# PFC_Controller.net
KiCad netlist of a schematic drawn in Altium Designer
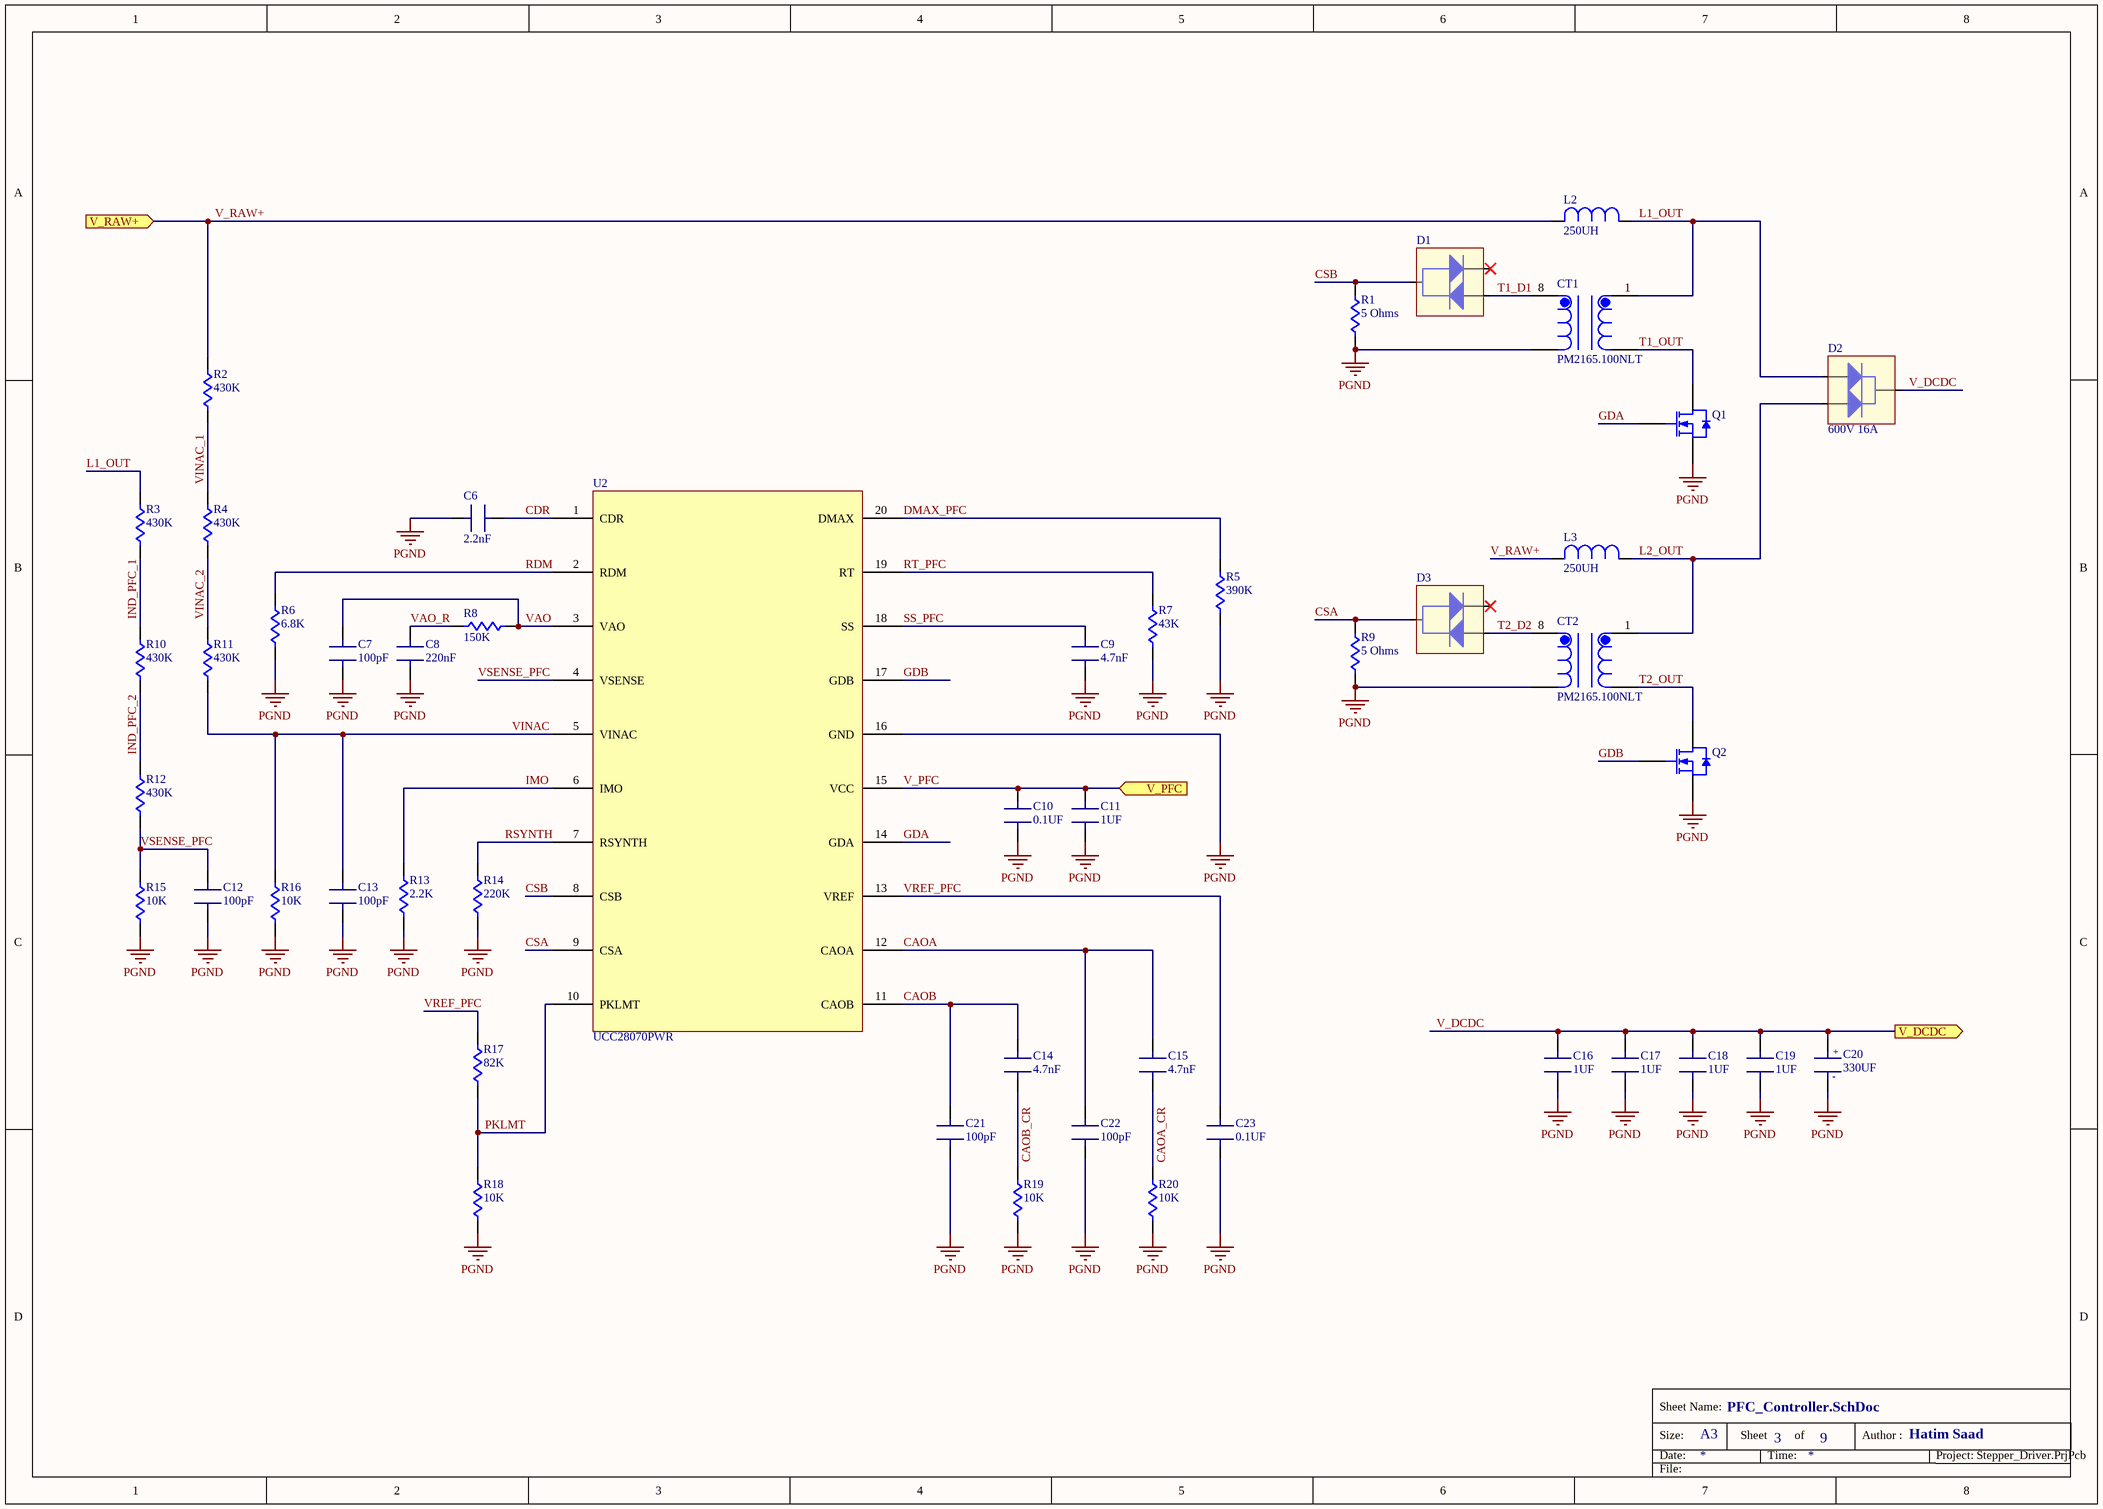
[diagram p0: PFC_Controller.SchDoc]

(export (version "E")
  (design (tool "Eeschema 10.0.6"))
  (components
    (comp (ref "C6")
      (value "2.2nF")
      (footprint "CAP: 0603")
      (description "CAP SMD 0603")
      (libsource (lib "HZSchLib") (part "CAP 0603"))
    )
    (comp (ref "C7")
      (value "100pF")
      (footprint "CAP: 0603")
      (description "CAP SMD 0603")
      (libsource (lib "HZSchLib") (part "CAP 0603"))
    )
    (comp (ref "C8")
      (value "220nF")
      (footprint "CAP: 0603")
      (description "CAP SMD 0603")
      (libsource (lib "HZSchLib") (part "CAP 0603"))
    )
    (comp (ref "C9")
      (value "4.7nF")
      (footprint "CAP: 0603")
      (description "CAP SMD 0603")
      (libsource (lib "HZSchLib") (part "CAP 0603"))
    )
    (comp (ref "C10")
      (value "0.1UF")
      (footprint "CAP: 0603")
      (description "CAP SMD 0603")
      (libsource (lib "HZSchLib") (part "CAP 0603"))
    )
    (comp (ref "C11")
      (value "1UF")
      (footprint "CAP: 0603")
      (description "CAP SMD 0603")
      (libsource (lib "HZSchLib") (part "CAP 0603"))
    )
    (comp (ref "C12")
      (value "100pF")
      (footprint "CAP: 0603")
      (description "CAP SMD 0603")
      (libsource (lib "HZSchLib") (part "CAP 0603"))
    )
    (comp (ref "C13")
      (value "100pF")
      (footprint "CAP: 0603")
      (description "CAP SMD 0603")
      (libsource (lib "HZSchLib") (part "CAP 0603"))
    )
    (comp (ref "C14")
      (value "4.7nF")
      (footprint "CAP: 0603")
      (description "CAP SMD 0603")
      (libsource (lib "HZSchLib") (part "CAP 0603"))
    )
    (comp (ref "C15")
      (value "4.7nF")
      (footprint "CAP: 0603")
      (description "CAP SMD 0603")
      (libsource (lib "HZSchLib") (part "CAP 0603"))
    )
    (comp (ref "C16")
      (value "1UF")
      (footprint "CAP: 2220")
      (description "Multilayer Ceramic Capacitors MLCC - SMD/SMT 1 uF 450 VDC 10% 2220 X7T")
      (libsource (lib "HZSchLib") (part "GR355XD7LP105KW05L"))
    )
    (comp (ref "C17")
      (value "1UF")
      (footprint "CAP: 2220")
      (description "Multilayer Ceramic Capacitors MLCC - SMD/SMT 1 uF 450 VDC 10% 2220 X7T")
      (libsource (lib "HZSchLib") (part "GR355XD7LP105KW05L"))
    )
    (comp (ref "C18")
      (value "1UF")
      (footprint "CAP: 2220")
      (description "Multilayer Ceramic Capacitors MLCC - SMD/SMT 1 uF 450 VDC 10% 2220 X7T")
      (libsource (lib "HZSchLib") (part "GR355XD7LP105KW05L"))
    )
    (comp (ref "C19")
      (value "1UF")
      (footprint "CAP: 2220")
      (description "Multilayer Ceramic Capacitors MLCC - SMD/SMT 1 uF 450 VDC 10% 2220 X7T")
      (libsource (lib "HZSchLib") (part "GR355XD7LP105KW05L"))
    )
    (comp (ref "C20")
      (value "330UF")
      (footprint "CAP: 10MM D: 35MM L: 25MM Snap In")
      (description "Aluminium Electrolytic Capacitors - Snap In 450V 330uF 20% Tol.")
      (libsource (lib "HZSchLib") (part "ESMR451VSN331MA25S"))
    )
    (comp (ref "C21")
      (value "100pF")
      (footprint "CAP: 0603")
      (description "CAP SMD 0603")
      (libsource (lib "HZSchLib") (part "CAP 0603"))
    )
    (comp (ref "C22")
      (value "100pF")
      (footprint "CAP: 0603")
      (description "CAP SMD 0603")
      (libsource (lib "HZSchLib") (part "CAP 0603"))
    )
    (comp (ref "C23")
      (value "0.1UF")
      (footprint "CAP: 0603")
      (description "CAP SMD 0603")
      (libsource (lib "HZSchLib") (part "CAP 0603"))
    )
    (comp (ref "CT1")
      (value "PM2165.100NLT")
      (footprint "CT: PM2165.100NLT")
      (description "Current Transformers 2mH 1000V AEC-Q200 20A DCR=0.75mOhms")
      (libsource (lib "HZSchLib") (part "PM2165.100NLT"))
    )
    (comp (ref "CT2")
      (value "PM2165.100NLT")
      (footprint "CT: PM2165.100NLT")
      (description "Current Transformers 2mH 1000V AEC-Q200 20A DCR=0.75mOhms")
      (libsource (lib "HZSchLib") (part "PM2165.100NLT"))
    )
    (comp (ref "D1")
      (value "BAT54SWT1G")
      (footprint "SOT323")
      (description "Schottky Diodes & Rectifiers 30V 200mW Dual")
      (libsource (lib "HZSchLib") (part "BAT54SWT1G"))
    )
    (comp (ref "D2")
      (value "600V 16A")
      (footprint "D2PAK")
      (description "Schottky Diodes & Rectifiers 600V 16A TO-263 HexFred")
      (libsource (lib "HZSchLib") (part "VS-HFA16TA60CS-M3"))
    )
    (comp (ref "D3")
      (value "BAT54SWT1G")
      (footprint "SOT323")
      (description "Schottky Diodes & Rectifiers 30V 200mW Dual")
      (libsource (lib "HZSchLib") (part "BAT54SWT1G"))
    )
    (comp (ref "L2")
      (value "250UH")
      (footprint "IND: ATCA-08-251M-H")
      (description "FIXED IND 250UH 10A 27 MOHM TH")
      (libsource (lib "HZSchLib") (part "ATCA-08-251M-H"))
    )
    (comp (ref "L3")
      (value "250UH")
      (footprint "IND: ATCA-08-251M-H")
      (description "FIXED IND 250UH 10A 27 MOHM TH")
      (libsource (lib "HZSchLib") (part "ATCA-08-251M-H"))
    )
    (comp (ref "Q1")
      (value "IPT60R099CM8XTMA1")
      (footprint "8-HSOF")
      (description "MOSFETs 600V CoolMOS CM8 Power Transistor")
      (libsource (lib "HZSchLib") (part "IPT60R099CM8XTMA1"))
    )
    (comp (ref "Q2")
      (value "IPT60R099CM8XTMA1")
      (footprint "8-HSOF")
      (description "MOSFETs 600V CoolMOS CM8 Power Transistor")
      (libsource (lib "HZSchLib") (part "IPT60R099CM8XTMA1"))
    )
    (comp (ref "R1")
      (value "5 Ohms")
      (footprint "RES: 1206")
      (description "Current Sense Resistors - SMD 5Ohms 1206 1W 1% Thin Curr Sens AEC-Q200")
      (libsource (lib "HZSchLib") (part "CSRT1206FT5R00"))
    )
    (comp (ref "R2")
      (value "430K")
      (footprint "RES: 2512")
      (description "RES SMD 2512")
      (libsource (lib "HZSchLib") (part "RES 2512"))
    )
    (comp (ref "R3")
      (value "430K")
      (footprint "RES: 2512")
      (description "RES SMD 2512")
      (libsource (lib "HZSchLib") (part "RES 2512"))
    )
    (comp (ref "R4")
      (value "430K")
      (footprint "RES: 2512")
      (description "RES SMD 2512")
      (libsource (lib "HZSchLib") (part "RES 2512"))
    )
    (comp (ref "R5")
      (value "390K")
      (footprint "RES: 0603")
      (description "RES SMD 0603")
      (libsource (lib "HZSchLib") (part "RES 0603"))
    )
    (comp (ref "R6")
      (value "6.8K")
      (footprint "RES: 0603")
      (description "RES SMD 0603")
      (libsource (lib "HZSchLib") (part "RES 0603"))
    )
    (comp (ref "R7")
      (value "43K")
      (footprint "RES: 0603")
      (description "RES SMD 0603")
      (libsource (lib "HZSchLib") (part "RES 0603"))
    )
    (comp (ref "R8")
      (value "150K")
      (footprint "RES: 0603")
      (description "RES SMD 0603")
      (libsource (lib "HZSchLib") (part "RES 0603"))
    )
    (comp (ref "R9")
      (value "5 Ohms")
      (footprint "RES: 1206")
      (description "Current Sense Resistors - SMD 5Ohms 1206 1W 1% Thin Curr Sens AEC-Q200")
      (libsource (lib "HZSchLib") (part "CSRT1206FT5R00"))
    )
    (comp (ref "R10")
      (value "430K")
      (footprint "RES: 2512")
      (description "RES SMD 2512")
      (libsource (lib "HZSchLib") (part "RES 2512"))
    )
    (comp (ref "R11")
      (value "430K")
      (footprint "RES: 2512")
      (description "RES SMD 2512")
      (libsource (lib "HZSchLib") (part "RES 2512"))
    )
    (comp (ref "R12")
      (value "430K")
      (footprint "RES: 2512")
      (description "RES SMD 2512")
      (libsource (lib "HZSchLib") (part "RES 2512"))
    )
    (comp (ref "R13")
      (value "2.2K")
      (footprint "RES: 0603")
      (description "RES SMD 0603")
      (libsource (lib "HZSchLib") (part "RES 0603"))
    )
    (comp (ref "R14")
      (value "220K")
      (footprint "RES: 0603")
      (description "RES SMD 0603")
      (libsource (lib "HZSchLib") (part "RES 0603"))
    )
    (comp (ref "R15")
      (value "10K")
      (footprint "RES: 0603")
      (description "RES SMD 0603")
      (libsource (lib "HZSchLib") (part "RES 0603"))
    )
    (comp (ref "R16")
      (value "10K")
      (footprint "RES: 0603")
      (description "RES SMD 0603")
      (libsource (lib "HZSchLib") (part "RES 0603"))
    )
    (comp (ref "R17")
      (value "82K")
      (footprint "RES: 0603")
      (description "RES SMD 0603")
      (libsource (lib "HZSchLib") (part "RES 0603"))
    )
    (comp (ref "R18")
      (value "10K")
      (footprint "RES: 0603")
      (description "RES SMD 0603")
      (libsource (lib "HZSchLib") (part "RES 0603"))
    )
    (comp (ref "R19")
      (value "10K")
      (footprint "RES: 0603")
      (description "RES SMD 0603")
      (libsource (lib "HZSchLib") (part "RES 0603"))
    )
    (comp (ref "R20")
      (value "10K")
      (footprint "RES: 0603")
      (description "RES SMD 0603")
      (libsource (lib "HZSchLib") (part "RES 0603"))
    )
    (comp (ref "U2")
      (value "UCC28070PWR")
      (footprint "20-TSSOP")
      (description "Power Factor Correction - PFC 2Phase Interleaved C CM PFC Controller A 595-UCC28070PW")
      (libsource (lib "HZSchLib") (part "UCC28070PWR"))
    )
  )
  (nets
    (net (code "1") (name "/CAOA") (class "Default")
      (node (ref "C15") (pin "2") (pinfunction "B_2") (pintype "passive"))
      (node (ref "C22") (pin "2") (pinfunction "B_2") (pintype "passive"))
      (node (ref "U2") (pin "12") (pinfunction "CAOA_12") (pintype "passive"))
    )
    (net (code "2") (name "/CAOA_CR") (class "Default")
      (node (ref "C15") (pin "1") (pinfunction "A_1") (pintype "passive"))
      (node (ref "R20") (pin "2") (pinfunction "2_2") (pintype "passive"))
    )
    (net (code "3") (name "/CAOB") (class "Default")
      (node (ref "C14") (pin "2") (pinfunction "B_2") (pintype "passive"))
      (node (ref "C21") (pin "2") (pinfunction "B_2") (pintype "passive"))
      (node (ref "U2") (pin "11") (pinfunction "CAOB_11") (pintype "passive"))
    )
    (net (code "4") (name "/CAOB_CR") (class "Default")
      (node (ref "C14") (pin "1") (pinfunction "A_1") (pintype "passive"))
      (node (ref "R19") (pin "2") (pinfunction "2_2") (pintype "passive"))
    )
    (net (code "5") (name "/CDR") (class "Default")
      (node (ref "C6") (pin "1") (pinfunction "A_1") (pintype "passive"))
      (node (ref "U2") (pin "1") (pinfunction "CDR_1") (pintype "passive"))
    )
    (net (code "6") (name "/CSA") (class "Default")
      (node (ref "D3") (pin "3") (pinfunction "A/K_3") (pintype "passive"))
      (node (ref "R9") (pin "2") (pinfunction "2_2") (pintype "passive"))
      (node (ref "U2") (pin "9") (pinfunction "CSA_9") (pintype "passive"))
    )
    (net (code "7") (name "/CSB") (class "Default")
      (node (ref "D1") (pin "3") (pinfunction "A/K_3") (pintype "passive"))
      (node (ref "R1") (pin "2") (pinfunction "2_2") (pintype "passive"))
      (node (ref "U2") (pin "8") (pinfunction "CSB_8") (pintype "passive"))
    )
    (net (code "8") (name "/DMAX_PFC") (class "Default")
      (node (ref "R5") (pin "2") (pinfunction "2_2") (pintype "passive"))
      (node (ref "U2") (pin "20") (pinfunction "DMAX_20") (pintype "passive"))
    )
    (net (code "9") (name "/GDA") (class "Default")
      (node (ref "Q1") (pin "1") (pinfunction "G_1") (pintype "passive"))
      (node (ref "U2") (pin "14") (pinfunction "GDA_14") (pintype "passive"))
    )
    (net (code "10") (name "/GDB") (class "Default")
      (node (ref "Q2") (pin "1") (pinfunction "G_1") (pintype "passive"))
      (node (ref "U2") (pin "17") (pinfunction "GDB_17") (pintype "passive"))
    )
    (net (code "11") (name "/IMO") (class "Default")
      (node (ref "R13") (pin "2") (pinfunction "2_2") (pintype "passive"))
      (node (ref "U2") (pin "6") (pinfunction "IMO_6") (pintype "passive"))
    )
    (net (code "12") (name "/IND_PFC_1") (class "Default")
      (node (ref "R10") (pin "2") (pinfunction "2_2") (pintype "passive"))
      (node (ref "R3") (pin "1") (pinfunction "1_1") (pintype "passive"))
    )
    (net (code "13") (name "/IND_PFC_2") (class "Default")
      (node (ref "R10") (pin "1") (pinfunction "1_1") (pintype "passive"))
      (node (ref "R12") (pin "2") (pinfunction "2_2") (pintype "passive"))
    )
    (net (code "14") (name "/L1_OUT") (class "Default")
      (node (ref "CT1") (pin "1") (pinfunction "P_1") (pintype "passive"))
      (node (ref "D2") (pin "1") (pinfunction "A_1") (pintype "passive"))
      (node (ref "L2") (pin "2") (pinfunction "2_2") (pintype "passive"))
      (node (ref "R3") (pin "2") (pinfunction "2_2") (pintype "passive"))
    )
    (net (code "15") (name "/L2_OUT") (class "Default")
      (node (ref "CT2") (pin "1") (pinfunction "P_1") (pintype "passive"))
      (node (ref "D2") (pin "3") (pinfunction "A_3") (pintype "passive"))
      (node (ref "L3") (pin "2") (pinfunction "2_2") (pintype "passive"))
    )
    (net (code "16") (name "/PKLMT") (class "Default")
      (node (ref "R17") (pin "1") (pinfunction "1_1") (pintype "passive"))
      (node (ref "R18") (pin "2") (pinfunction "2_2") (pintype "passive"))
      (node (ref "U2") (pin "10") (pinfunction "PKLMT_10") (pintype "passive"))
    )
    (net (code "17") (name "/RDM") (class "Default")
      (node (ref "R6") (pin "2") (pinfunction "2_2") (pintype "passive"))
      (node (ref "U2") (pin "2") (pinfunction "RDM_2") (pintype "passive"))
    )
    (net (code "18") (name "/RSYNTH") (class "Default")
      (node (ref "R14") (pin "2") (pinfunction "2_2") (pintype "passive"))
      (node (ref "U2") (pin "7") (pinfunction "RSYNTH_7") (pintype "passive"))
    )
    (net (code "19") (name "/RT_PFC") (class "Default")
      (node (ref "R7") (pin "2") (pinfunction "2_2") (pintype "passive"))
      (node (ref "U2") (pin "19") (pinfunction "RT_19") (pintype "passive"))
    )
    (net (code "20") (name "/SS_PFC") (class "Default")
      (node (ref "C9") (pin "2") (pinfunction "B_2") (pintype "passive"))
      (node (ref "U2") (pin "18") (pinfunction "SS_18") (pintype "passive"))
    )
    (net (code "21") (name "/T1_D1") (class "Default")
      (node (ref "CT1") (pin "8") (pinfunction "S_8") (pintype "passive"))
      (node (ref "D1") (pin "1") (pinfunction "A_1") (pintype "passive"))
    )
    (net (code "22") (name "/T1_OUT") (class "Default")
      (node (ref "CT1") (pin "3") (pinfunction "P_3") (pintype "passive"))
      (node (ref "Q1") (pin "2") (pinfunction "D_2") (pintype "passive"))
    )
    (net (code "23") (name "/T2_D2") (class "Default")
      (node (ref "CT2") (pin "8") (pinfunction "S_8") (pintype "passive"))
      (node (ref "D3") (pin "1") (pinfunction "A_1") (pintype "passive"))
    )
    (net (code "24") (name "/T2_OUT") (class "Default")
      (node (ref "CT2") (pin "3") (pinfunction "P_3") (pintype "passive"))
      (node (ref "Q2") (pin "2") (pinfunction "D_2") (pintype "passive"))
    )
    (net (code "25") (name "/VAO") (class "Default")
      (node (ref "C7") (pin "2") (pinfunction "B_2") (pintype "passive"))
      (node (ref "R8") (pin "2") (pinfunction "2_2") (pintype "passive"))
      (node (ref "U2") (pin "3") (pinfunction "VAO_3") (pintype "passive"))
    )
    (net (code "26") (name "/VAO_R") (class "Default")
      (node (ref "C8") (pin "2") (pinfunction "B_2") (pintype "passive"))
      (node (ref "R8") (pin "1") (pinfunction "1_1") (pintype "passive"))
    )
    (net (code "27") (name "/VINAC") (class "Default")
      (node (ref "C13") (pin "2") (pinfunction "B_2") (pintype "passive"))
      (node (ref "R11") (pin "1") (pinfunction "1_1") (pintype "passive"))
      (node (ref "R16") (pin "2") (pinfunction "2_2") (pintype "passive"))
      (node (ref "U2") (pin "5") (pinfunction "VINAC_5") (pintype "passive"))
    )
    (net (code "28") (name "/VINAC_1") (class "Default")
      (node (ref "R2") (pin "1") (pinfunction "1_1") (pintype "passive"))
      (node (ref "R4") (pin "2") (pinfunction "2_2") (pintype "passive"))
    )
    (net (code "29") (name "/VINAC_2") (class "Default")
      (node (ref "R11") (pin "2") (pinfunction "2_2") (pintype "passive"))
      (node (ref "R4") (pin "1") (pinfunction "1_1") (pintype "passive"))
    )
    (net (code "30") (name "/VREF_PFC") (class "Default")
      (node (ref "C23") (pin "2") (pinfunction "B_2") (pintype "passive"))
      (node (ref "R17") (pin "2") (pinfunction "2_2") (pintype "passive"))
      (node (ref "U2") (pin "13") (pinfunction "VREF_13") (pintype "passive"))
    )
    (net (code "31") (name "/VSENSE_PFC") (class "Default")
      (node (ref "C12") (pin "2") (pinfunction "B_2") (pintype "passive"))
      (node (ref "R12") (pin "1") (pinfunction "1_1") (pintype "passive"))
      (node (ref "R15") (pin "2") (pinfunction "2_2") (pintype "passive"))
      (node (ref "U2") (pin "4") (pinfunction "VSENSE_4") (pintype "passive"))
    )
    (net (code "32") (name "/V_DCDC") (class "Default")
      (node (ref "C16") (pin "2") (pinfunction "B_2") (pintype "passive"))
      (node (ref "C17") (pin "2") (pinfunction "B_2") (pintype "passive"))
      (node (ref "C18") (pin "2") (pinfunction "B_2") (pintype "passive"))
      (node (ref "C19") (pin "2") (pinfunction "B_2") (pintype "passive"))
      (node (ref "C20") (pin "1") (pinfunction "+_1") (pintype "passive"))
      (node (ref "D2") (pin "2") (pinfunction "K_2") (pintype "passive"))
    )
    (net (code "33") (name "/V_PFC") (class "Default")
      (node (ref "C10") (pin "2") (pinfunction "B_2") (pintype "passive"))
      (node (ref "C11") (pin "2") (pinfunction "B_2") (pintype "passive"))
      (node (ref "U2") (pin "15") (pinfunction "VCC_15") (pintype "passive"))
    )
    (net (code "34") (name "/V_RAW+") (class "Default")
      (node (ref "L2") (pin "1") (pinfunction "1_1") (pintype "passive"))
      (node (ref "L3") (pin "1") (pinfunction "1_1") (pintype "passive"))
      (node (ref "R2") (pin "2") (pinfunction "2_2") (pintype "passive"))
    )
    (net (code "35") (name "PGND") (class "Default")
      (node (ref "C10") (pin "1") (pinfunction "A_1") (pintype "passive"))
      (node (ref "C11") (pin "1") (pinfunction "A_1") (pintype "passive"))
      (node (ref "C12") (pin "1") (pinfunction "A_1") (pintype "passive"))
      (node (ref "C13") (pin "1") (pinfunction "A_1") (pintype "passive"))
      (node (ref "C16") (pin "1") (pinfunction "A_1") (pintype "passive"))
      (node (ref "C17") (pin "1") (pinfunction "A_1") (pintype "passive"))
      (node (ref "C18") (pin "1") (pinfunction "A_1") (pintype "passive"))
      (node (ref "C19") (pin "1") (pinfunction "A_1") (pintype "passive"))
      (node (ref "C20") (pin "2") (pinfunction "-_2") (pintype "passive"))
      (node (ref "C21") (pin "1") (pinfunction "A_1") (pintype "passive"))
      (node (ref "C22") (pin "1") (pinfunction "A_1") (pintype "passive"))
      (node (ref "C23") (pin "1") (pinfunction "A_1") (pintype "passive"))
      (node (ref "C6") (pin "2") (pinfunction "B_2") (pintype "passive"))
      (node (ref "C7") (pin "1") (pinfunction "A_1") (pintype "passive"))
      (node (ref "C8") (pin "1") (pinfunction "A_1") (pintype "passive"))
      (node (ref "C9") (pin "1") (pinfunction "A_1") (pintype "passive"))
      (node (ref "CT1") (pin "7") (pinfunction "S_7") (pintype "passive"))
      (node (ref "CT2") (pin "7") (pinfunction "S_7") (pintype "passive"))
      (node (ref "Q1") (pin "3") (pinfunction "S_3") (pintype "passive"))
      (node (ref "Q2") (pin "3") (pinfunction "S_3") (pintype "passive"))
      (node (ref "R1") (pin "1") (pinfunction "1_1") (pintype "passive"))
      (node (ref "R13") (pin "1") (pinfunction "1_1") (pintype "passive"))
      (node (ref "R14") (pin "1") (pinfunction "1_1") (pintype "passive"))
      (node (ref "R15") (pin "1") (pinfunction "1_1") (pintype "passive"))
      (node (ref "R16") (pin "1") (pinfunction "1_1") (pintype "passive"))
      (node (ref "R18") (pin "1") (pinfunction "1_1") (pintype "passive"))
      (node (ref "R19") (pin "1") (pinfunction "1_1") (pintype "passive"))
      (node (ref "R20") (pin "1") (pinfunction "1_1") (pintype "passive"))
      (node (ref "R5") (pin "1") (pinfunction "1_1") (pintype "passive"))
      (node (ref "R6") (pin "1") (pinfunction "1_1") (pintype "passive"))
      (node (ref "R7") (pin "1") (pinfunction "1_1") (pintype "passive"))
      (node (ref "R9") (pin "1") (pinfunction "1_1") (pintype "passive"))
      (node (ref "U2") (pin "16") (pinfunction "GND_16") (pintype "passive"))
    )
    (net (code "36") (name "unconnected-(D1-K-Pad2)") (class "Default")
      (node (ref "D1") (pin "2") (pinfunction "K_2") (pintype "passive+no_connect"))
    )
    (net (code "37") (name "unconnected-(D3-K-Pad2)") (class "Default")
      (node (ref "D3") (pin "2") (pinfunction "K_2") (pintype "passive+no_connect"))
    )
  )
)
